# power.net
KiCad netlist of a schematic drawn in Altium Designer
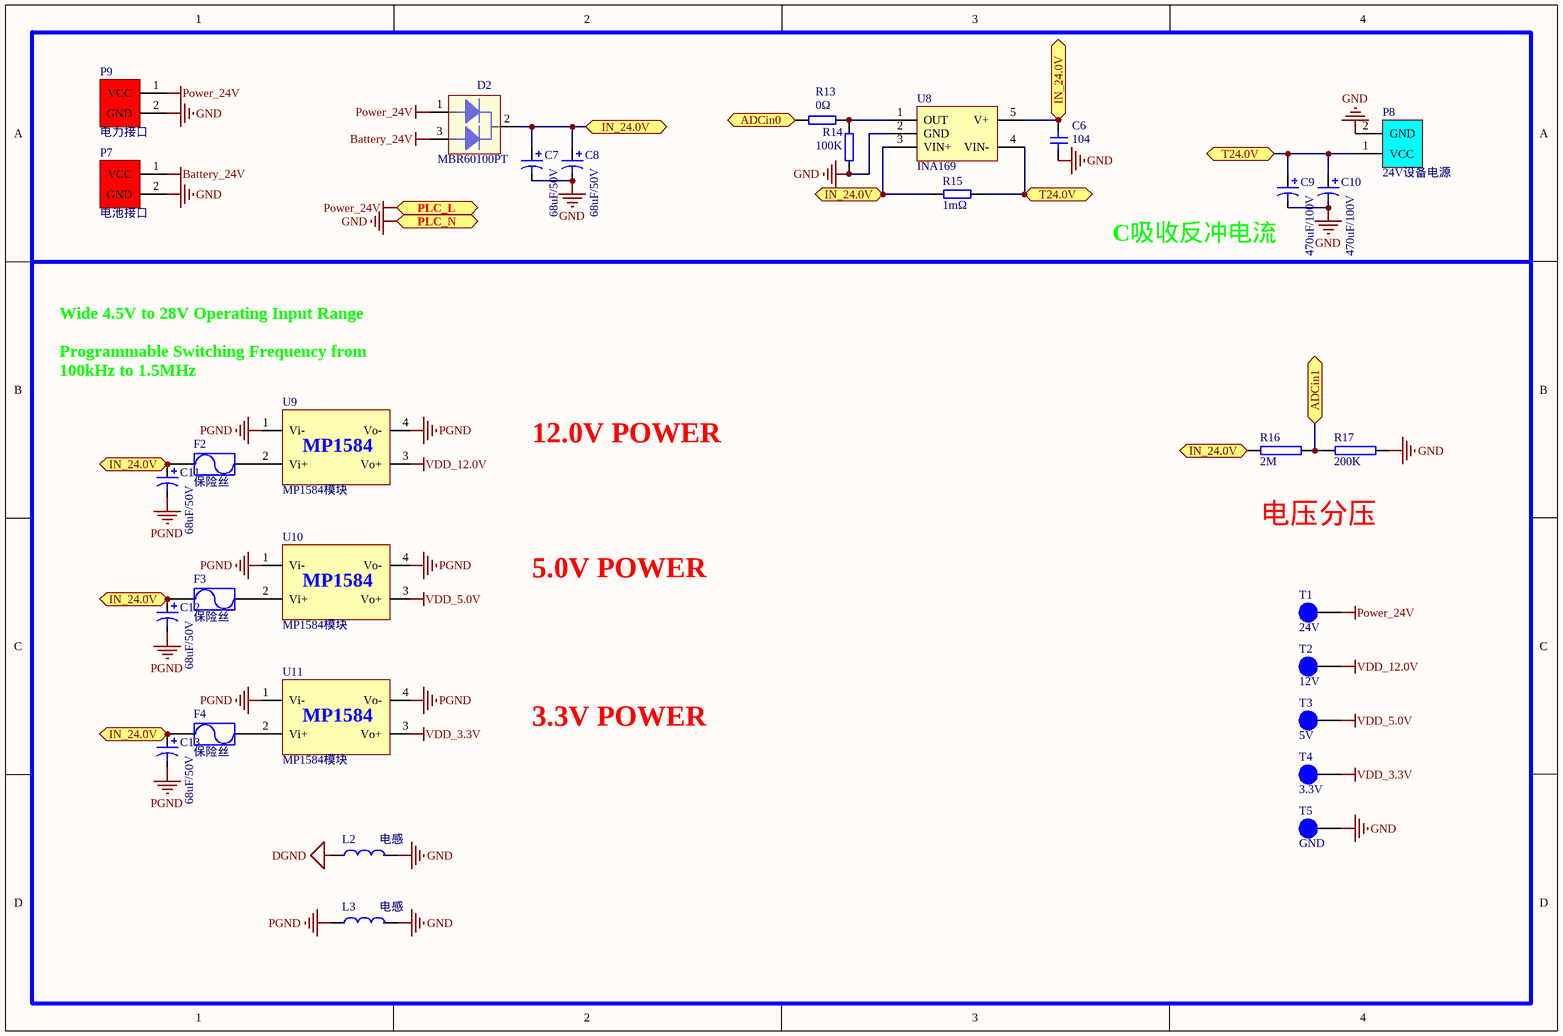
[diagram p0: power.SchDoc]

(export (version "E")
  (design (tool "Eeschema 10.0.6"))
  (components
    (comp (ref "C6")
      (value "104")
      (footprint "0805C")
      (description "无极贴片电容")
      (libsource (lib "集大电协1.5") (part "Cap1"))
    )
    (comp (ref "C7")
      (value "68uF/50V")
      (footprint "RB.2.4")
      (description "直插极性电容")
      (libsource (lib "集大电协1.5") (part "Cap3"))
    )
    (comp (ref "C8")
      (value "68uF/50V")
      (footprint "RB.2.4")
      (description "直插极性电容")
      (libsource (lib "集大电协1.5") (part "Cap3"))
    )
    (comp (ref "C9")
      (value "470uF/100V")
      (footprint "RB.1.2")
      (description "直插极性电容")
      (libsource (lib "集大电协1.5") (part "Cap3"))
    )
    (comp (ref "C10")
      (value "470uF/100V")
      (footprint "RB.1.2")
      (description "直插极性电容")
      (libsource (lib "集大电协1.5") (part "Cap3"))
    )
    (comp (ref "C11")
      (value "68uF/50V")
      (footprint "RB.1.2")
      (description "直插极性电容")
      (libsource (lib "集大电协1.5") (part "Cap3"))
    )
    (comp (ref "C12")
      (value "68uF/50V")
      (footprint "RB.1.2")
      (description "直插极性电容")
      (libsource (lib "集大电协1.5") (part "Cap3"))
    )
    (comp (ref "C13")
      (value "68uF/50V")
      (footprint "RB.1.2")
      (description "直插极性电容")
      (libsource (lib "集大电协1.5") (part "Cap3"))
    )
    (comp (ref "D2")
      (value "MBR60100PT")
      (footprint "TO-247LS")
      (libsource (lib "集大电协1.5") (part "MBR60100PT"))
    )
    (comp (ref "F2") (value "保险丝") (footprint "FUSE-1812") (libsource (lib "集大电协1.5") (part "Fuse")))
    (comp (ref "F3") (value "保险丝") (footprint "FUSE-1812") (libsource (lib "集大电协1.5") (part "Fuse")))
    (comp (ref "F4") (value "保险丝") (footprint "FUSE-1812") (libsource (lib "集大电协1.5") (part "Fuse")))
    (comp (ref "L2") (value "电感") (footprint "1206L") (libsource (lib "集大电协1.5") (part "L")))
    (comp (ref "L3") (value "电感") (footprint "1206L") (libsource (lib "集大电协1.5") (part "L")))
    (comp (ref "P7") (value "电池接口") (footprint "XT60-F") (libsource (lib "集大电协1.5") (part "电源端子")))
    (comp (ref "P8") (value "24V设备电源") (footprint "XT60-F") (libsource (lib "集大电协1.5") (part "推进器电源")))
    (comp (ref "P9") (value "电力接口") (footprint "XT60-F") (libsource (lib "集大电协1.5") (part "电源端子")))
    (comp (ref "R13")
      (value "0Ω")
      (footprint "0805R")
      (description "电阻")
      (libsource (lib "集大电协1.5") (part "Res"))
    )
    (comp (ref "R14")
      (value "100K")
      (footprint "0805R")
      (description "电阻")
      (libsource (lib "集大电协1.5") (part "Res"))
    )
    (comp (ref "R15")
      (value "1mΩ")
      (footprint "2512R")
      (description "电阻")
      (libsource (lib "集大电协1.5") (part "Res"))
    )
    (comp (ref "R16") (value "2M") (footprint "0805R") (libsource (lib "窝牛器件封装") (part "R1")))
    (comp (ref "R17") (value "200K") (footprint "0805R") (libsource (lib "窝牛器件封装") (part "R1")))
    (comp (ref "T1")
      (value "24V")
      (footprint "HEADER 1")
      (description "测试点")
      (libsource (lib "集大电协1.2") (part "测试点"))
    )
    (comp (ref "T2")
      (value "12V")
      (footprint "HEADER 1")
      (description "测试点")
      (libsource (lib "集大电协1.2") (part "测试点"))
    )
    (comp (ref "T3")
      (value "5V")
      (footprint "HEADER 1")
      (description "测试点")
      (libsource (lib "集大电协1.2") (part "测试点"))
    )
    (comp (ref "T4")
      (value "3.3V")
      (footprint "HEADER 1")
      (description "测试点")
      (libsource (lib "集大电协1.2") (part "测试点"))
    )
    (comp (ref "T5")
      (value "GND")
      (footprint "HEADER 1")
      (description "测试点")
      (libsource (lib "集大电协1.2") (part "测试点"))
    )
    (comp (ref "U8") (value "INA169") (footprint "SOT23-5") (libsource (lib "集大电协1.5") (part "INA169")))
    (comp (ref "U9")
      (value "MP1584模块")
      (footprint "MP1584电源模块")
      (libsource (lib "集大电协1.5") (part "MP1584电源模块"))
    )
    (comp (ref "U10")
      (value "MP1584模块")
      (footprint "MP1584电源模块")
      (libsource (lib "集大电协1.5") (part "MP1584电源模块"))
    )
    (comp (ref "U11")
      (value "MP1584模块")
      (footprint "MP1584电源模块")
      (libsource (lib "集大电协1.5") (part "MP1584电源模块"))
    )
  )
  (nets
    (net (code "1") (name "/ADCin0") (class "Default")
      (node (ref "R13") (pin "1") (pinfunction "1_1") (pintype "passive"))
    )
    (net (code "2") (name "/ADCin1") (class "Default")
      (node (ref "R16") (pin "2") (pinfunction "2_2") (pintype "passive"))
      (node (ref "R17") (pin "1") (pinfunction "1_1") (pintype "passive"))
    )
    (net (code "3") (name "/IN_24.0V") (class "Default")
      (node (ref "C11") (pin "1") (pinfunction "1_1") (pintype "passive"))
      (node (ref "C12") (pin "1") (pinfunction "1_1") (pintype "passive"))
      (node (ref "C13") (pin "1") (pinfunction "1_1") (pintype "passive"))
      (node (ref "C6") (pin "2") (pinfunction "2_2") (pintype "passive"))
      (node (ref "C7") (pin "1") (pinfunction "1_1") (pintype "passive"))
      (node (ref "C8") (pin "1") (pinfunction "1_1") (pintype "passive"))
      (node (ref "D2") (pin "2") (pinfunction "2_2") (pintype "passive"))
      (node (ref "F2") (pin "1") (pinfunction "1_1") (pintype "passive"))
      (node (ref "F3") (pin "1") (pinfunction "1_1") (pintype "passive"))
      (node (ref "F4") (pin "1") (pinfunction "1_1") (pintype "passive"))
      (node (ref "R15") (pin "2") (pinfunction "2_2") (pintype "passive"))
      (node (ref "R16") (pin "1") (pinfunction "1_1") (pintype "passive"))
      (node (ref "U8") (pin "3") (pinfunction "VIN+_3") (pintype "passive"))
      (node (ref "U8") (pin "5") (pinfunction "V+_5") (pintype "passive"))
    )
    (net (code "4") (name "/T24.0V") (class "Default")
      (node (ref "C10") (pin "1") (pinfunction "1_1") (pintype "passive"))
      (node (ref "C9") (pin "1") (pinfunction "1_1") (pintype "passive"))
      (node (ref "P8") (pin "1") (pinfunction "VCC_1") (pintype "passive"))
      (node (ref "R15") (pin "1") (pinfunction "1_1") (pintype "passive"))
      (node (ref "U8") (pin "4") (pinfunction "VIN-_4") (pintype "passive"))
    )
    (net (code "5") (name "Battery_24V") (class "Default")
      (node (ref "D2") (pin "3") (pintype "passive"))
      (node (ref "P7") (pin "1") (pinfunction "VCC_1") (pintype "passive"))
    )
    (net (code "6") (name "DGND") (class "Default")
      (node (ref "L2") (pin "1") (pinfunction "1_1") (pintype "passive"))
    )
    (net (code "7") (name "GND") (class "Default")
      (node (ref "C10") (pin "2") (pinfunction "2_2") (pintype "passive"))
      (node (ref "C6") (pin "1") (pinfunction "1_1") (pintype "passive"))
      (node (ref "C7") (pin "2") (pinfunction "2_2") (pintype "passive"))
      (node (ref "C8") (pin "2") (pinfunction "2_2") (pintype "passive"))
      (node (ref "C9") (pin "2") (pinfunction "2_2") (pintype "passive"))
      (node (ref "L2") (pin "2") (pinfunction "2_2") (pintype "passive"))
      (node (ref "L3") (pin "2") (pinfunction "2_2") (pintype "passive"))
      (node (ref "P7") (pin "2") (pinfunction "GND_2") (pintype "passive"))
      (node (ref "P8") (pin "2") (pinfunction "GND_2") (pintype "passive"))
      (node (ref "P9") (pin "2") (pinfunction "GND_2") (pintype "passive"))
      (node (ref "R14") (pin "2") (pinfunction "2_2") (pintype "passive"))
      (node (ref "R17") (pin "2") (pinfunction "2_2") (pintype "passive"))
      (node (ref "T5") (pin "1") (pinfunction "1_1") (pintype "passive"))
      (node (ref "U8") (pin "2") (pinfunction "GND_2") (pintype "passive"))
    )
    (net (code "8") (name "Net-(U8-OUT)") (class "Default")
      (node (ref "R13") (pin "2") (pinfunction "2_2") (pintype "passive"))
      (node (ref "R14") (pin "1") (pinfunction "1_1") (pintype "passive"))
      (node (ref "U8") (pin "1") (pinfunction "OUT_1") (pintype "passive"))
    )
    (net (code "9") (name "Net-(U9-Vi+)") (class "Default")
      (node (ref "F2") (pin "2") (pinfunction "2_2") (pintype "passive"))
      (node (ref "U9") (pin "2") (pinfunction "Vi+_2") (pintype "passive"))
    )
    (net (code "10") (name "Net-(U10-Vi+)") (class "Default")
      (node (ref "F3") (pin "2") (pinfunction "2_2") (pintype "passive"))
      (node (ref "U10") (pin "2") (pinfunction "Vi+_2") (pintype "passive"))
    )
    (net (code "11") (name "Net-(U11-Vi+)") (class "Default")
      (node (ref "F4") (pin "2") (pinfunction "2_2") (pintype "passive"))
      (node (ref "U11") (pin "2") (pinfunction "Vi+_2") (pintype "passive"))
    )
    (net (code "12") (name "PGND") (class "Default")
      (node (ref "C11") (pin "2") (pinfunction "2_2") (pintype "passive"))
      (node (ref "C12") (pin "2") (pinfunction "2_2") (pintype "passive"))
      (node (ref "C13") (pin "2") (pinfunction "2_2") (pintype "passive"))
      (node (ref "L3") (pin "1") (pinfunction "1_1") (pintype "passive"))
      (node (ref "U10") (pin "1") (pinfunction "Vi-_1") (pintype "passive"))
      (node (ref "U10") (pin "4") (pinfunction "Vo-_4") (pintype "passive"))
      (node (ref "U11") (pin "1") (pinfunction "Vi-_1") (pintype "passive"))
      (node (ref "U11") (pin "4") (pinfunction "Vo-_4") (pintype "passive"))
      (node (ref "U9") (pin "1") (pinfunction "Vi-_1") (pintype "passive"))
      (node (ref "U9") (pin "4") (pinfunction "Vo-_4") (pintype "passive"))
    )
    (net (code "13") (name "Power_24V") (class "Default")
      (node (ref "D2") (pin "1") (pintype "passive"))
      (node (ref "P9") (pin "1") (pinfunction "VCC_1") (pintype "passive"))
      (node (ref "T1") (pin "1") (pinfunction "1_1") (pintype "passive"))
    )
    (net (code "14") (name "VDD_3.3V") (class "Default")
      (node (ref "T4") (pin "1") (pinfunction "1_1") (pintype "passive"))
      (node (ref "U11") (pin "3") (pinfunction "Vo+_3") (pintype "passive"))
    )
    (net (code "15") (name "VDD_5.0V") (class "Default")
      (node (ref "T3") (pin "1") (pinfunction "1_1") (pintype "passive"))
      (node (ref "U10") (pin "3") (pinfunction "Vo+_3") (pintype "passive"))
    )
    (net (code "16") (name "VDD_12.0V") (class "Default")
      (node (ref "T2") (pin "1") (pinfunction "1_1") (pintype "passive"))
      (node (ref "U9") (pin "3") (pinfunction "Vo+_3") (pintype "passive"))
    )
  )
)
